# 000-_SCH_PCB_CheeseCake-BMI270-AUX.net
KiCad netlist of a schematic drawn in EasyEDA Pro
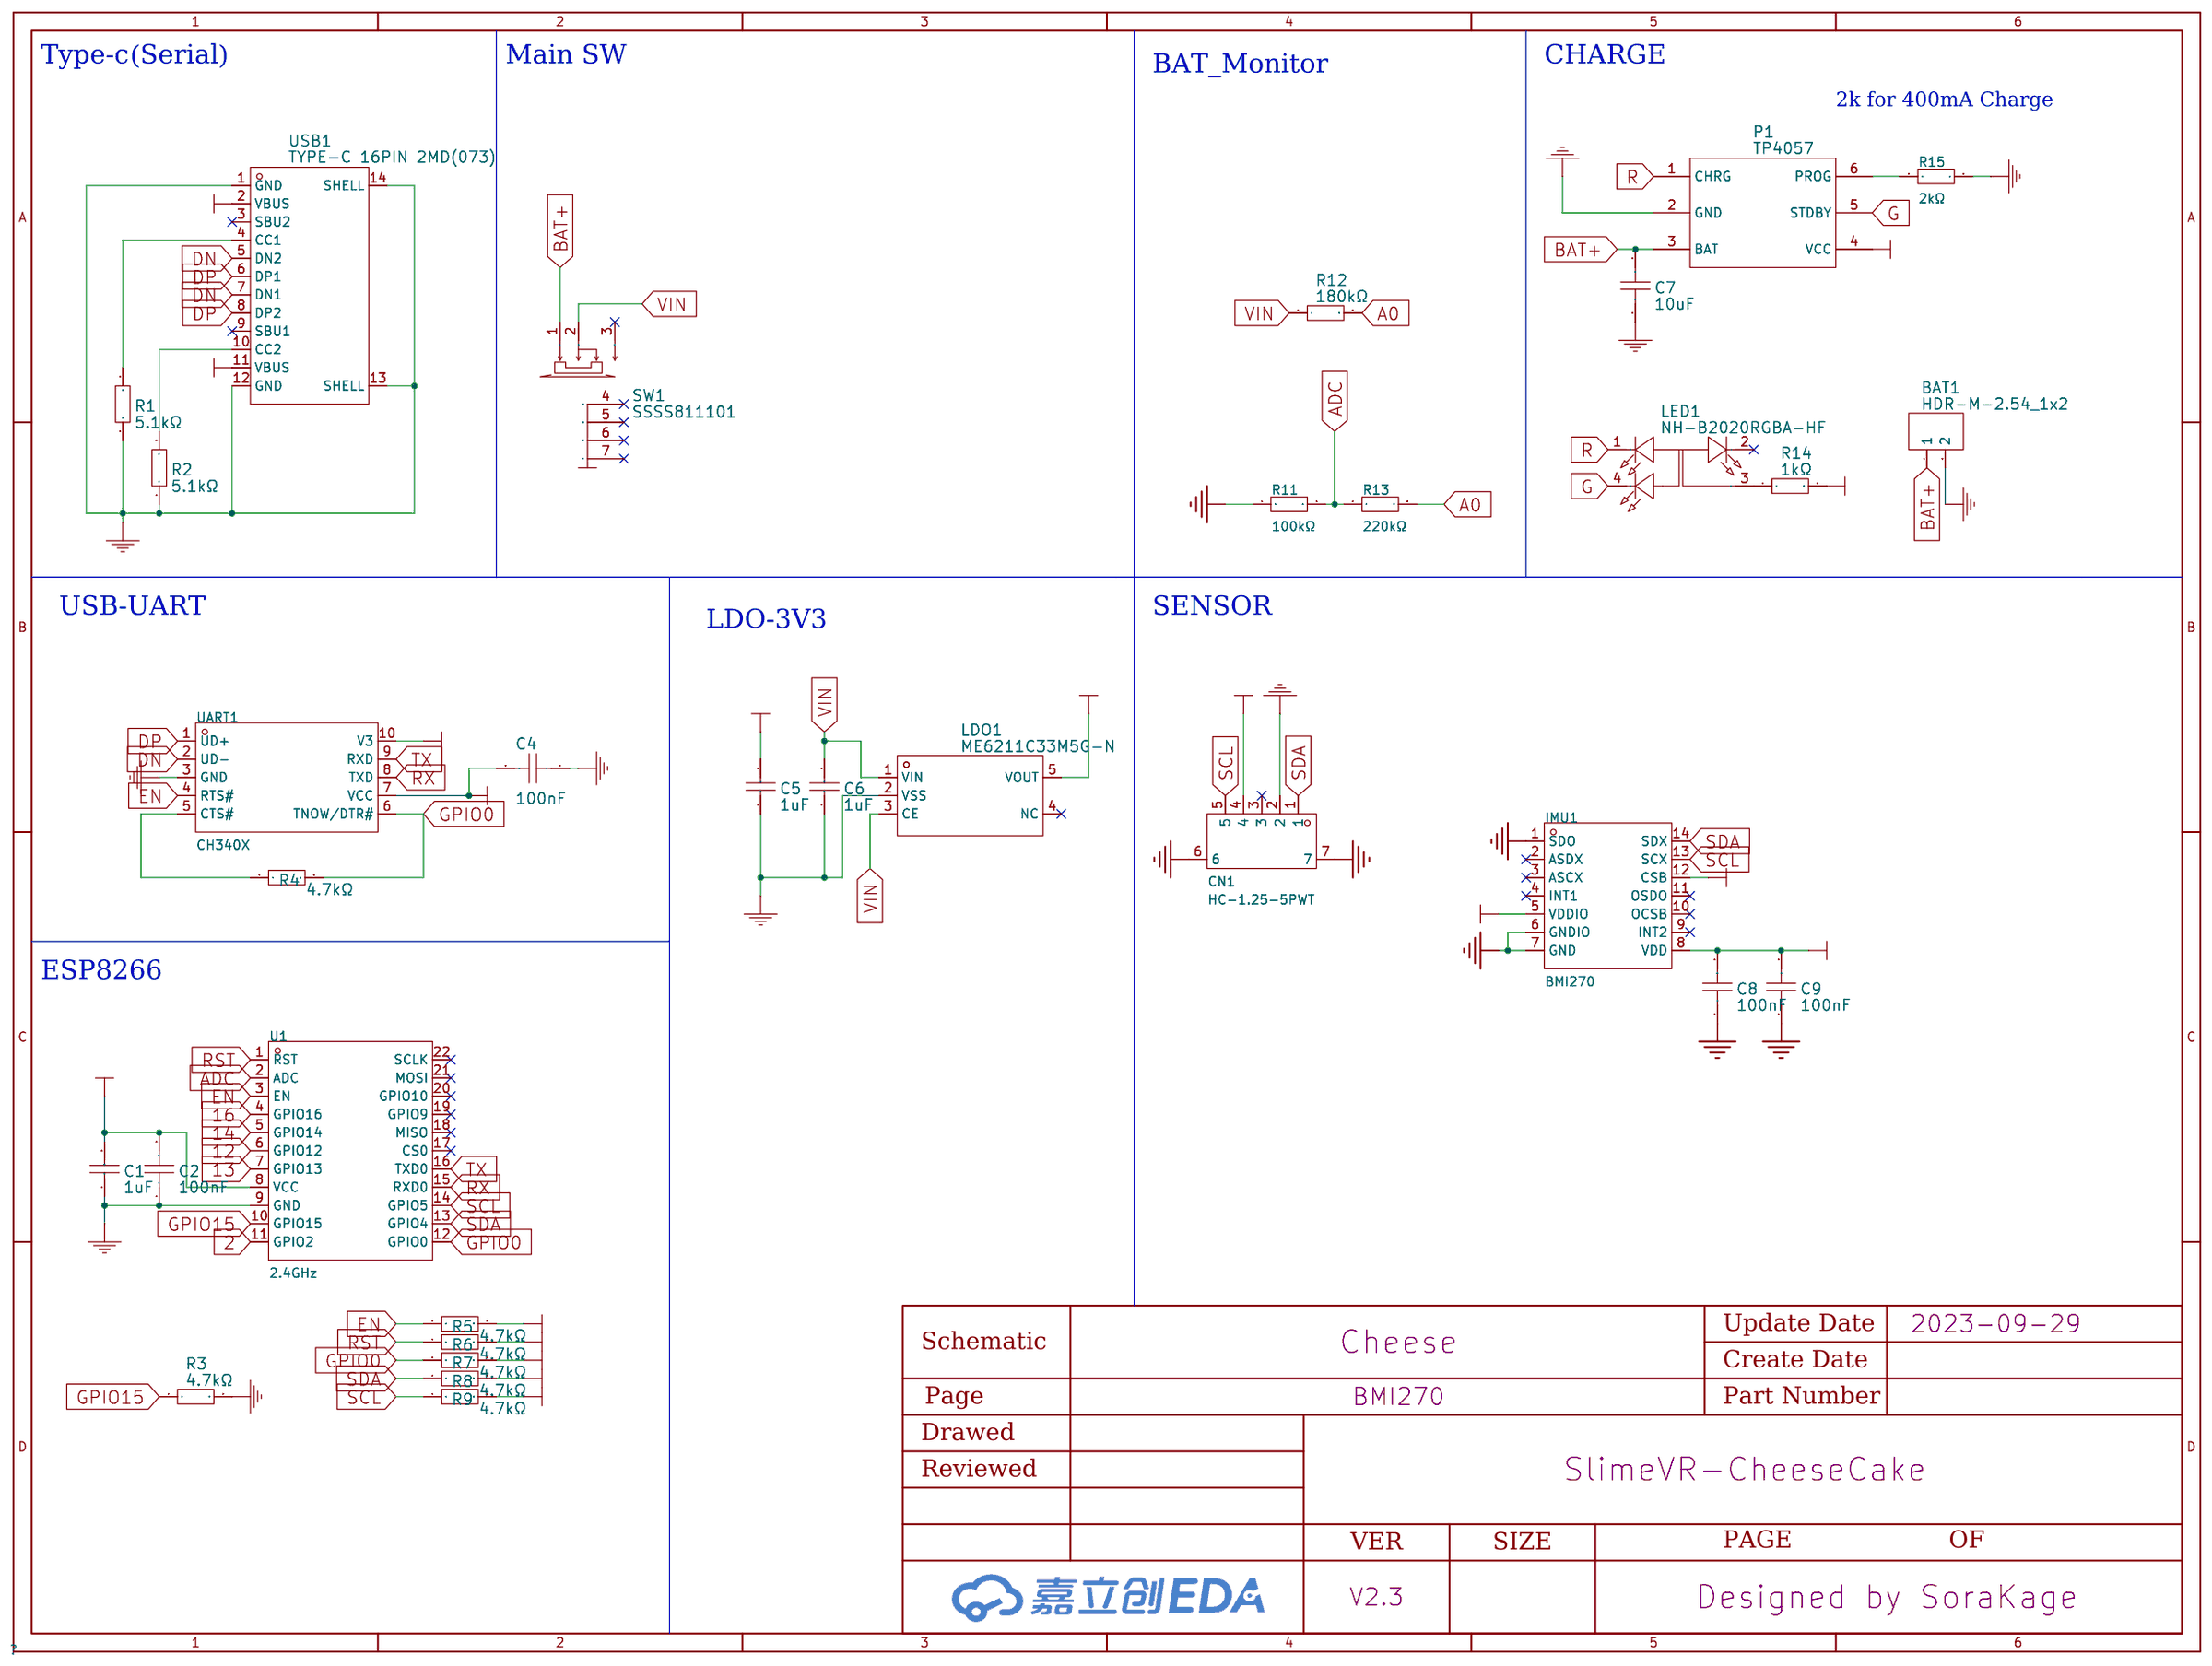
[diagram p0: schematic sheet]

(export (version "E")
  (design (tool "Eeschema 10.0.6"))
  (components
    (comp (ref "BAT1")
      (value "HDR-M-2.54_1x2")
      (footprint "easyedapro:HDR-M-2.54_1X2")
      (libsource (lib "easyedapro") (part "HDR-M-2.54_1x2"))
    )
    (comp (ref "C1")
      (value "1uF")
      (footprint "easyedapro:C0603")
      (fields
        (field (name "Manufacturer Part") "CL10A105KB8NNNC")
        (field (name "Manufacturer") "SAMSUNG(三星)")
      )
      (libsource (lib "easyedapro") (part "1uF"))
    )
    (comp (ref "C2")
      (value "100nF")
      (footprint "easyedapro:C0603")
      (fields
        (field (name "Manufacturer Part") "CC0603KRX7R9BB104")
        (field (name "Manufacturer") "YAGEO(国巨)")
      )
      (libsource (lib "easyedapro") (part "100nF"))
    )
    (comp (ref "C4")
      (value "100nF")
      (footprint "easyedapro:C0603")
      (fields
        (field (name "Manufacturer Part") "CC0603KRX7R9BB104")
        (field (name "Manufacturer") "YAGEO(国巨)")
      )
      (libsource (lib "easyedapro") (part "100nF"))
    )
    (comp (ref "C5")
      (value "1uF")
      (footprint "easyedapro:C0603")
      (fields
        (field (name "Manufacturer Part") "CL10A105KB8NNNC")
        (field (name "Manufacturer") "SAMSUNG(三星)")
      )
      (libsource (lib "easyedapro") (part "1uF"))
    )
    (comp (ref "C6")
      (value "1uF")
      (footprint "easyedapro:C0603")
      (fields
        (field (name "Manufacturer Part") "CL10A105KB8NNNC")
        (field (name "Manufacturer") "SAMSUNG(三星)")
      )
      (libsource (lib "easyedapro") (part "1uF"))
    )
    (comp (ref "C7")
      (value "10uF")
      (footprint "easyedapro:C0603")
      (fields
        (field (name "Manufacturer Part") "CL10A106KP8NNNC")
        (field (name "Manufacturer") "SAMSUNG(三星)")
      )
      (libsource (lib "easyedapro") (part "10uF"))
    )
    (comp (ref "C8")
      (value "100nF")
      (footprint "easyedapro:C0603")
      (fields
        (field (name "Manufacturer Part") "CC0603KRX7R9BB104")
        (field (name "Manufacturer") "YAGEO(国巨)")
      )
      (libsource (lib "easyedapro") (part "100nF"))
    )
    (comp (ref "C9")
      (value "100nF")
      (footprint "easyedapro:C0603")
      (fields
        (field (name "Manufacturer Part") "CC0603KRX7R9BB104")
        (field (name "Manufacturer") "YAGEO(国巨)")
      )
      (libsource (lib "easyedapro") (part "100nF"))
    )
    (comp (ref "CN1")
      (value "HC-1.25-5PWT")
      (footprint "easyedapro:CONN-SMD_5P-P1.25_HCTL_HC-1.25-5PWT")
      (description "参考系列:-;间距:1.25mm;插针结构:1x5P;排数:1;每排PIN数:5;行距:-;公母:公型插针;安装方式:卧贴;额定电流:1A;工作温度范围:-25°C~+85°C;")
      (fields (field (name "Manufacturer") "HCTL(华灿天禄)"))
      (libsource (lib "easyedapro") (part "HC-1.25-5PWT"))
    )
    (comp (ref "IMU1")
      (value "BMI270")
      (footprint "easyedapro:LGA-14_L3.0-W2.5-P0.50-BR")
      (description "IMU-惯性测量单元")
      (fields (field (name "Manufacturer") "Bosch(博世)"))
      (libsource (lib "easyedapro") (part "BMI270"))
    )
    (comp (ref "LDO1")
      (value "ME6211C33M5G-N")
      (footprint "easyedapro:SOT-23-5_L3.0-W1.7-P0.95-LS2.8-BR")
      (fields (field (name "Manufacturer") "MICRONE"))
      (libsource (lib "easyedapro") (part "ME6211C33M5G-N"))
    )
    (comp (ref "LED1")
      (value "NH-B2020RGBA-HF")
      (footprint "easyedapro:LED-ARRAY-SMD_4P-L2.1-W2.1-TL_NH-B2020RGBA")
      (fields (field (name "Manufacturer") "国星光电"))
      (libsource (lib "easyedapro") (part "NH-B2020RGBA-HF"))
    )
    (comp (ref "P1")
      (value "TP4057")
      (fields
        (field (name "Manufacturer Part") "TP4057-42-SOT26-R")
        (field (name "Manufacturer") "TOPPOWER(南京拓微)")
      )
      (libsource (lib "easyedapro") (part "TP4057"))
    )
    (comp (ref "R1")
      (value "5.1kΩ")
      (footprint "easyedapro:R0603")
      (fields
        (field (name "Manufacturer Part") "0603WAF5101T5E")
        (field (name "Manufacturer") "UNI-ROYAL(厚声)")
      )
      (libsource (lib "easyedapro") (part "5.1kΩ"))
    )
    (comp (ref "R2")
      (value "5.1kΩ")
      (footprint "easyedapro:R0603")
      (fields
        (field (name "Manufacturer Part") "0603WAF5101T5E")
        (field (name "Manufacturer") "UNI-ROYAL(厚声)")
      )
      (libsource (lib "easyedapro") (part "5.1kΩ"))
    )
    (comp (ref "R3")
      (value "4.7kΩ")
      (footprint "easyedapro:R0603")
      (fields
        (field (name "Manufacturer Part") "0603WAF4701T5E")
        (field (name "Manufacturer") "UNI-ROYAL(厚声)")
      )
      (libsource (lib "easyedapro") (part "4.7kΩ"))
    )
    (comp (ref "R4")
      (value "4.7kΩ")
      (footprint "easyedapro:R0603")
      (fields
        (field (name "Manufacturer Part") "0603WAF4701T5E")
        (field (name "Manufacturer") "UNI-ROYAL(厚声)")
      )
      (libsource (lib "easyedapro") (part "4.7kΩ"))
    )
    (comp (ref "R5")
      (value "4.7kΩ")
      (footprint "easyedapro:R0603")
      (fields
        (field (name "Manufacturer Part") "0603WAF4701T5E")
        (field (name "Manufacturer") "UNI-ROYAL(厚声)")
      )
      (libsource (lib "easyedapro") (part "4.7kΩ"))
    )
    (comp (ref "R6")
      (value "4.7kΩ")
      (footprint "easyedapro:R0603")
      (fields
        (field (name "Manufacturer Part") "0603WAF4701T5E")
        (field (name "Manufacturer") "UNI-ROYAL(厚声)")
      )
      (libsource (lib "easyedapro") (part "4.7kΩ"))
    )
    (comp (ref "R7")
      (value "4.7kΩ")
      (footprint "easyedapro:R0603")
      (fields
        (field (name "Manufacturer Part") "0603WAF4701T5E")
        (field (name "Manufacturer") "UNI-ROYAL(厚声)")
      )
      (libsource (lib "easyedapro") (part "4.7kΩ"))
    )
    (comp (ref "R8")
      (value "4.7kΩ")
      (footprint "easyedapro:R0603")
      (fields
        (field (name "Manufacturer Part") "0603WAF4701T5E")
        (field (name "Manufacturer") "UNI-ROYAL(厚声)")
      )
      (libsource (lib "easyedapro") (part "4.7kΩ"))
    )
    (comp (ref "R9")
      (value "4.7kΩ")
      (footprint "easyedapro:R0603")
      (fields
        (field (name "Manufacturer Part") "0603WAF4701T5E")
        (field (name "Manufacturer") "UNI-ROYAL(厚声)")
      )
      (libsource (lib "easyedapro") (part "4.7kΩ"))
    )
    (comp (ref "R11")
      (value "100kΩ")
      (footprint "easyedapro:R0603")
      (description "电阻类型:厚膜电阻;阻值:100kΩ;精度:±1%;功率:100mW;")
      (fields
        (field (name "Manufacturer Part") "0603WAF1003T5E")
        (field (name "Manufacturer") "UNI-ROYAL(厚声)")
      )
      (libsource (lib "easyedapro") (part "0603WAF1003T5E"))
    )
    (comp (ref "R12")
      (value "180kΩ")
      (footprint "easyedapro:R0603")
      (fields
        (field (name "Manufacturer Part") "0603WAF1803T5E")
        (field (name "Manufacturer") "UNI-ROYAL(厚声)")
      )
      (libsource (lib "easyedapro") (part "180kΩ"))
    )
    (comp (ref "R13")
      (value "220kΩ")
      (footprint "easyedapro:R0603")
      (description "电阻类型:厚膜电阻;阻值:220kΩ;精度:±1%;功率:100mW;")
      (fields
        (field (name "Manufacturer Part") "0603WAF2203T5E")
        (field (name "Manufacturer") "UNI-ROYAL(厚声)")
      )
      (libsource (lib "easyedapro") (part "0603WAF2203T5E"))
    )
    (comp (ref "R14")
      (value "1kΩ")
      (footprint "easyedapro:R0603")
      (fields
        (field (name "Manufacturer Part") "0603WAF1001T5E")
        (field (name "Manufacturer") "UNI-ROYAL(厚声)")
      )
      (libsource (lib "easyedapro") (part "1kΩ"))
    )
    (comp (ref "R15")
      (value "2kΩ")
      (footprint "easyedapro:R0603")
      (description "电阻类型:厚膜电阻;阻值:2kΩ;精度:±1%;功率:100mW;")
      (fields
        (field (name "Manufacturer Part") "0603WAF2001T5E")
        (field (name "Manufacturer") "UNI-ROYAL(厚声)")
      )
      (libsource (lib "easyedapro") (part "0603WAF2001T5E"))
    )
    (comp (ref "SW1")
      (value "SSSS811101")
      (footprint "easyedapro:SW-SMD_SSSS811101")
      (fields (field (name "Manufacturer") "ALPSALPINE(阿尔卑斯阿尔派)"))
      (libsource (lib "easyedapro") (part "SSSS811101"))
    )
    (comp (ref "U1")
      (value "2.4GHz")
      (footprint "easyedapro:WIFIM-SMD_ESP-12F-ESP8266MOD")
      (description "频率:2.4GHz;发射功率:16dBm;核心处理器:ESP8266;天线形式:PCB 板载天线;接收灵敏度:-90dBm;")
      (fields
        (field (name "Manufacturer Part") "ESP-12F(ESP8266MOD)")
        (field (name "Manufacturer") "Ai-Thinker(安信可)")
      )
      (libsource (lib "easyedapro") (part "ESP-12F(ESP8266MOD)"))
    )
    (comp (ref "UART1")
      (value "CH340X")
      (footprint "easyedapro:MSOP-10_L3.0-W3.0-P0.50-LS5.0-BL")
      (fields (field (name "Manufacturer") "WCH(南京沁恒)"))
      (libsource (lib "easyedapro") (part "CH340X"))
    )
    (comp (ref "USB1")
      (value "TYPE-C 16PIN 2MD(073)")
      (footprint "easyedapro:USB-C-SMD_TYPE-C-6PIN-2MD-073")
      (fields (field (name "Manufacturer") "SHOU HAN(首韩)"))
      (libsource (lib "easyedapro") (part "TYPE-C 16PIN 2MD(073)"))
    )
  )
  (nets
    (net (code "1") (name "+5V") (class "Default")
      (node (ref "P1") (pin "4") (pinfunction "VCC_4") (pintype "input"))
      (node (ref "R14") (pin "2") (pinfunction "2_2") (pintype "input"))
      (node (ref "USB1") (pin "11") (pinfunction "VBUS_11") (pintype "input"))
      (node (ref "USB1") (pin "2") (pinfunction "VBUS_2") (pintype "input"))
    )
    (net (code "2") (name "2") (class "Default")
      (node (ref "U1") (pin "11") (pinfunction "GPIO2_11") (pintype "input"))
    )
    (net (code "3") (name "3V3") (class "Default")
      (node (ref "C1") (pin "2") (pinfunction "2_2") (pintype "input"))
      (node (ref "C2") (pin "2") (pinfunction "2_2") (pintype "input"))
      (node (ref "C4") (pin "2") (pinfunction "2_2") (pintype "input"))
      (node (ref "C5") (pin "2") (pinfunction "2_2") (pintype "input"))
      (node (ref "C8") (pin "2") (pinfunction "2_2") (pintype "input"))
      (node (ref "C9") (pin "2") (pinfunction "2_2") (pintype "input"))
      (node (ref "CN1") (pin "4") (pinfunction "4_4") (pintype "input"))
      (node (ref "IMU1") (pin "12") (pinfunction "CSB_12") (pintype "input"))
      (node (ref "IMU1") (pin "5") (pinfunction "VDDIO_5") (pintype "input"))
      (node (ref "IMU1") (pin "8") (pinfunction "VDD_8") (pintype "input"))
      (node (ref "LDO1") (pin "5") (pinfunction "VOUT_5") (pintype "input"))
      (node (ref "R5") (pin "2") (pinfunction "2_2") (pintype "input"))
      (node (ref "R6") (pin "2") (pinfunction "2_2") (pintype "input"))
      (node (ref "R7") (pin "2") (pinfunction "2_2") (pintype "input"))
      (node (ref "R8") (pin "2") (pinfunction "2_2") (pintype "input"))
      (node (ref "R9") (pin "2") (pinfunction "2_2") (pintype "input"))
      (node (ref "U1") (pin "8") (pinfunction "VCC_8") (pintype "input"))
      (node (ref "UART1") (pin "10") (pinfunction "V3_10") (pintype "input"))
      (node (ref "UART1") (pin "7") (pinfunction "VCC_7") (pintype "input"))
    )
    (net (code "4") (name "12") (class "Default")
      (node (ref "U1") (pin "6") (pinfunction "GPIO12_6") (pintype "input"))
    )
    (net (code "5") (name "13") (class "Default")
      (node (ref "U1") (pin "7") (pinfunction "GPIO13_7") (pintype "input"))
    )
    (net (code "6") (name "14") (class "Default")
      (node (ref "U1") (pin "5") (pinfunction "GPIO14_5") (pintype "input"))
    )
    (net (code "7") (name "16") (class "Default")
      (node (ref "U1") (pin "4") (pinfunction "GPIO16_4") (pintype "input"))
    )
    (net (code "8") (name "A0") (class "Default")
      (node (ref "R12") (pin "2") (pinfunction "2_2") (pintype "input"))
      (node (ref "R13") (pin "2") (pinfunction "2_2") (pintype "input"))
    )
    (net (code "9") (name "ADC") (class "Default")
      (node (ref "R11") (pin "2") (pinfunction "2_2") (pintype "input"))
      (node (ref "R13") (pin "1") (pinfunction "1_1") (pintype "input"))
      (node (ref "U1") (pin "2") (pinfunction "ADC_2") (pintype "input"))
    )
    (net (code "10") (name "BAT+") (class "Default")
      (node (ref "BAT1") (pin "1") (pinfunction "1_1") (pintype "input"))
      (node (ref "C7") (pin "2") (pinfunction "2_2") (pintype "input"))
      (node (ref "P1") (pin "3") (pinfunction "BAT_3") (pintype "input"))
      (node (ref "SW1") (pin "1") (pinfunction "1_1") (pintype "input"))
    )
    (net (code "11") (name "DN") (class "Default")
      (node (ref "UART1") (pin "2") (pinfunction "UD-_2") (pintype "input"))
      (node (ref "USB1") (pin "5") (pinfunction "DN2_5") (pintype "input"))
      (node (ref "USB1") (pin "7") (pinfunction "DN1_7") (pintype "input"))
    )
    (net (code "12") (name "DP") (class "Default")
      (node (ref "UART1") (pin "1") (pinfunction "UD+_1") (pintype "input"))
      (node (ref "USB1") (pin "6") (pinfunction "DP1_6") (pintype "input"))
      (node (ref "USB1") (pin "8") (pinfunction "DP2_8") (pintype "input"))
    )
    (net (code "13") (name "EN") (class "Default")
      (node (ref "R5") (pin "1") (pinfunction "1_1") (pintype "input"))
      (node (ref "U1") (pin "3") (pinfunction "EN_3") (pintype "input"))
      (node (ref "UART1") (pin "4") (pinfunction "RTS#_4") (pintype "input"))
    )
    (net (code "14") (name "G") (class "Default")
      (node (ref "LED1") (pin "4") (pinfunction "-_4") (pintype "input"))
      (node (ref "P1") (pin "5") (pinfunction "STDBY_5") (pintype "input"))
    )
    (net (code "15") (name "GND") (class "Default")
      (node (ref "BAT1") (pin "2") (pinfunction "2_2") (pintype "input"))
      (node (ref "C1") (pin "1") (pinfunction "1_1") (pintype "input"))
      (node (ref "C2") (pin "1") (pinfunction "1_1") (pintype "input"))
      (node (ref "C4") (pin "1") (pinfunction "1_1") (pintype "input"))
      (node (ref "C5") (pin "1") (pinfunction "1_1") (pintype "input"))
      (node (ref "C6") (pin "1") (pinfunction "1_1") (pintype "input"))
      (node (ref "C7") (pin "1") (pinfunction "1_1") (pintype "input"))
      (node (ref "C8") (pin "1") (pinfunction "1_1") (pintype "input"))
      (node (ref "C9") (pin "1") (pinfunction "1_1") (pintype "input"))
      (node (ref "CN1") (pin "2") (pinfunction "2_2") (pintype "input"))
      (node (ref "CN1") (pin "6") (pinfunction "6_6") (pintype "input"))
      (node (ref "CN1") (pin "7") (pinfunction "7_7") (pintype "input"))
      (node (ref "IMU1") (pin "1") (pinfunction "SDO_1") (pintype "input"))
      (node (ref "IMU1") (pin "6") (pinfunction "GNDIO_6") (pintype "input"))
      (node (ref "IMU1") (pin "7") (pinfunction "GND_7") (pintype "input"))
      (node (ref "LDO1") (pin "2") (pinfunction "VSS_2") (pintype "input"))
      (node (ref "P1") (pin "2") (pinfunction "GND_2") (pintype "input"))
      (node (ref "R1") (pin "1") (pinfunction "1_1") (pintype "input"))
      (node (ref "R11") (pin "1") (pinfunction "1_1") (pintype "input"))
      (node (ref "R15") (pin "2") (pinfunction "2_2") (pintype "input"))
      (node (ref "R2") (pin "1") (pinfunction "1_1") (pintype "input"))
      (node (ref "R3") (pin "2") (pinfunction "2_2") (pintype "input"))
      (node (ref "U1") (pin "9") (pinfunction "GND_9") (pintype "input"))
      (node (ref "UART1") (pin "3") (pinfunction "GND_3") (pintype "input"))
      (node (ref "USB1") (pin "1") (pinfunction "GND_1") (pintype "input"))
      (node (ref "USB1") (pin "12") (pinfunction "GND_12") (pintype "input"))
      (node (ref "USB1") (pin "13") (pinfunction "SHELL_13") (pintype "input"))
      (node (ref "USB1") (pin "14") (pinfunction "SHELL_14") (pintype "input"))
    )
    (net (code "16") (name "GPIO0") (class "Default")
      (node (ref "R4") (pin "2") (pinfunction "2_2") (pintype "input"))
      (node (ref "R7") (pin "1") (pinfunction "1_1") (pintype "input"))
      (node (ref "U1") (pin "12") (pinfunction "GPIO0_12") (pintype "input"))
      (node (ref "UART1") (pin "6") (pinfunction "TNOW/DTR#_6") (pintype "input"))
    )
    (net (code "17") (name "GPIO15") (class "Default")
      (node (ref "R3") (pin "1") (pinfunction "1_1") (pintype "input"))
      (node (ref "U1") (pin "10") (pinfunction "GPIO15_10") (pintype "input"))
    )
    (net (code "18") (name "Net-(LED1-+)") (class "Default")
      (node (ref "LED1") (pin "3") (pinfunction "+_3") (pintype "input"))
      (node (ref "R14") (pin "1") (pinfunction "1_1") (pintype "input"))
    )
    (net (code "19") (name "Net-(P1-PROG)") (class "Default")
      (node (ref "P1") (pin "6") (pinfunction "PROG_6") (pintype "input"))
      (node (ref "R15") (pin "1") (pinfunction "1_1") (pintype "input"))
    )
    (net (code "20") (name "Net-(UART1-CTS#)") (class "Default")
      (node (ref "R4") (pin "1") (pinfunction "1_1") (pintype "input"))
      (node (ref "UART1") (pin "5") (pinfunction "CTS#_5") (pintype "input"))
    )
    (net (code "21") (name "Net-(USB1-CC1)") (class "Default")
      (node (ref "R1") (pin "2") (pinfunction "2_2") (pintype "input"))
      (node (ref "USB1") (pin "4") (pinfunction "CC1_4") (pintype "input"))
    )
    (net (code "22") (name "Net-(USB1-CC2)") (class "Default")
      (node (ref "R2") (pin "2") (pinfunction "2_2") (pintype "input"))
      (node (ref "USB1") (pin "10") (pinfunction "CC2_10") (pintype "input"))
    )
    (net (code "23") (name "R") (class "Default")
      (node (ref "LED1") (pin "1") (pinfunction "-_1") (pintype "input"))
      (node (ref "P1") (pin "1") (pinfunction "CHRG_1") (pintype "input"))
    )
    (net (code "24") (name "RST") (class "Default")
      (node (ref "R6") (pin "1") (pinfunction "1_1") (pintype "input"))
      (node (ref "U1") (pin "1") (pinfunction "RST_1") (pintype "input"))
    )
    (net (code "25") (name "RX") (class "Default")
      (node (ref "U1") (pin "15") (pinfunction "RXD0_15") (pintype "input"))
      (node (ref "UART1") (pin "8") (pinfunction "TXD_8") (pintype "input"))
    )
    (net (code "26") (name "SCL") (class "Default")
      (node (ref "CN1") (pin "5") (pinfunction "5_5") (pintype "input"))
      (node (ref "IMU1") (pin "13") (pinfunction "SCX_13") (pintype "input"))
      (node (ref "R9") (pin "1") (pinfunction "1_1") (pintype "input"))
      (node (ref "U1") (pin "14") (pinfunction "GPIO5_14") (pintype "input"))
    )
    (net (code "27") (name "SDA") (class "Default")
      (node (ref "CN1") (pin "1") (pinfunction "1_1") (pintype "input"))
      (node (ref "IMU1") (pin "14") (pinfunction "SDX_14") (pintype "input"))
      (node (ref "R8") (pin "1") (pinfunction "1_1") (pintype "input"))
      (node (ref "U1") (pin "13") (pinfunction "GPIO4_13") (pintype "input"))
    )
    (net (code "28") (name "TX") (class "Default")
      (node (ref "U1") (pin "16") (pinfunction "TXD0_16") (pintype "input"))
      (node (ref "UART1") (pin "9") (pinfunction "RXD_9") (pintype "input"))
    )
    (net (code "29") (name "VIN") (class "Default")
      (node (ref "C6") (pin "2") (pinfunction "2_2") (pintype "input"))
      (node (ref "LDO1") (pin "1") (pinfunction "VIN_1") (pintype "input"))
      (node (ref "LDO1") (pin "3") (pinfunction "CE_3") (pintype "input"))
      (node (ref "R12") (pin "1") (pinfunction "1_1") (pintype "input"))
      (node (ref "SW1") (pin "2") (pinfunction "2_2") (pintype "input"))
    )
    (net (code "30") (name "unconnected-(CN1-Pad3)") (class "Default")
      (node (ref "CN1") (pin "3") (pinfunction "3_3") (pintype "input+no_connect"))
    )
    (net (code "31") (name "unconnected-(IMU1-ASCX-Pad3)") (class "Default")
      (node (ref "IMU1") (pin "3") (pinfunction "ASCX_3") (pintype "input+no_connect"))
    )
    (net (code "32") (name "unconnected-(IMU1-ASDX-Pad2)") (class "Default")
      (node (ref "IMU1") (pin "2") (pinfunction "ASDX_2") (pintype "input+no_connect"))
    )
    (net (code "33") (name "unconnected-(IMU1-INT1-Pad4)") (class "Default")
      (node (ref "IMU1") (pin "4") (pinfunction "INT1_4") (pintype "input+no_connect"))
    )
    (net (code "34") (name "unconnected-(IMU1-INT2-Pad9)") (class "Default")
      (node (ref "IMU1") (pin "9") (pinfunction "INT2_9") (pintype "input+no_connect"))
    )
    (net (code "35") (name "unconnected-(IMU1-OCSB-Pad10)") (class "Default")
      (node (ref "IMU1") (pin "10") (pinfunction "OCSB_10") (pintype "input+no_connect"))
    )
    (net (code "36") (name "unconnected-(IMU1-OSDO-Pad11)") (class "Default")
      (node (ref "IMU1") (pin "11") (pinfunction "OSDO_11") (pintype "input+no_connect"))
    )
    (net (code "37") (name "unconnected-(LDO1-NC-Pad4)") (class "Default")
      (node (ref "LDO1") (pin "4") (pinfunction "NC_4") (pintype "input+no_connect"))
    )
    (net (code "38") (name "unconnected-(LED1---Pad2)") (class "Default")
      (node (ref "LED1") (pin "2") (pinfunction "-_2") (pintype "input+no_connect"))
    )
    (net (code "39") (name "unconnected-(SW1-Pad3)") (class "Default")
      (node (ref "SW1") (pin "3") (pinfunction "3_3") (pintype "input+no_connect"))
    )
    (net (code "40") (name "unconnected-(SW1-Pad4)") (class "Default")
      (node (ref "SW1") (pin "4") (pinfunction "4_4") (pintype "input+no_connect"))
    )
    (net (code "41") (name "unconnected-(SW1-Pad5)") (class "Default")
      (node (ref "SW1") (pin "5") (pinfunction "5_5") (pintype "input+no_connect"))
    )
    (net (code "42") (name "unconnected-(SW1-Pad6)") (class "Default")
      (node (ref "SW1") (pin "6") (pinfunction "6_6") (pintype "input+no_connect"))
    )
    (net (code "43") (name "unconnected-(SW1-Pad7)") (class "Default")
      (node (ref "SW1") (pin "7") (pinfunction "7_7") (pintype "input+no_connect"))
    )
    (net (code "44") (name "unconnected-(U1-CS0-Pad17)") (class "Default")
      (node (ref "U1") (pin "17") (pinfunction "CS0_17") (pintype "input+no_connect"))
    )
    (net (code "45") (name "unconnected-(U1-GPIO9-Pad19)") (class "Default")
      (node (ref "U1") (pin "19") (pinfunction "GPIO9_19") (pintype "input+no_connect"))
    )
    (net (code "46") (name "unconnected-(U1-GPIO10-Pad20)") (class "Default")
      (node (ref "U1") (pin "20") (pinfunction "GPIO10_20") (pintype "input+no_connect"))
    )
    (net (code "47") (name "unconnected-(U1-MISO-Pad18)") (class "Default")
      (node (ref "U1") (pin "18") (pinfunction "MISO_18") (pintype "input+no_connect"))
    )
    (net (code "48") (name "unconnected-(U1-MOSI-Pad21)") (class "Default")
      (node (ref "U1") (pin "21") (pinfunction "MOSI_21") (pintype "input+no_connect"))
    )
    (net (code "49") (name "unconnected-(U1-SCLK-Pad22)") (class "Default")
      (node (ref "U1") (pin "22") (pinfunction "SCLK_22") (pintype "input+no_connect"))
    )
    (net (code "50") (name "unconnected-(USB1-SBU1-Pad9)") (class "Default")
      (node (ref "USB1") (pin "9") (pinfunction "SBU1_9") (pintype "input+no_connect"))
    )
    (net (code "51") (name "unconnected-(USB1-SBU2-Pad3)") (class "Default")
      (node (ref "USB1") (pin "3") (pinfunction "SBU2_3") (pintype "input+no_connect"))
    )
  )
)
